# Sheet___2025-11-01.net
KiCad netlist of a schematic drawn in Altium Designer
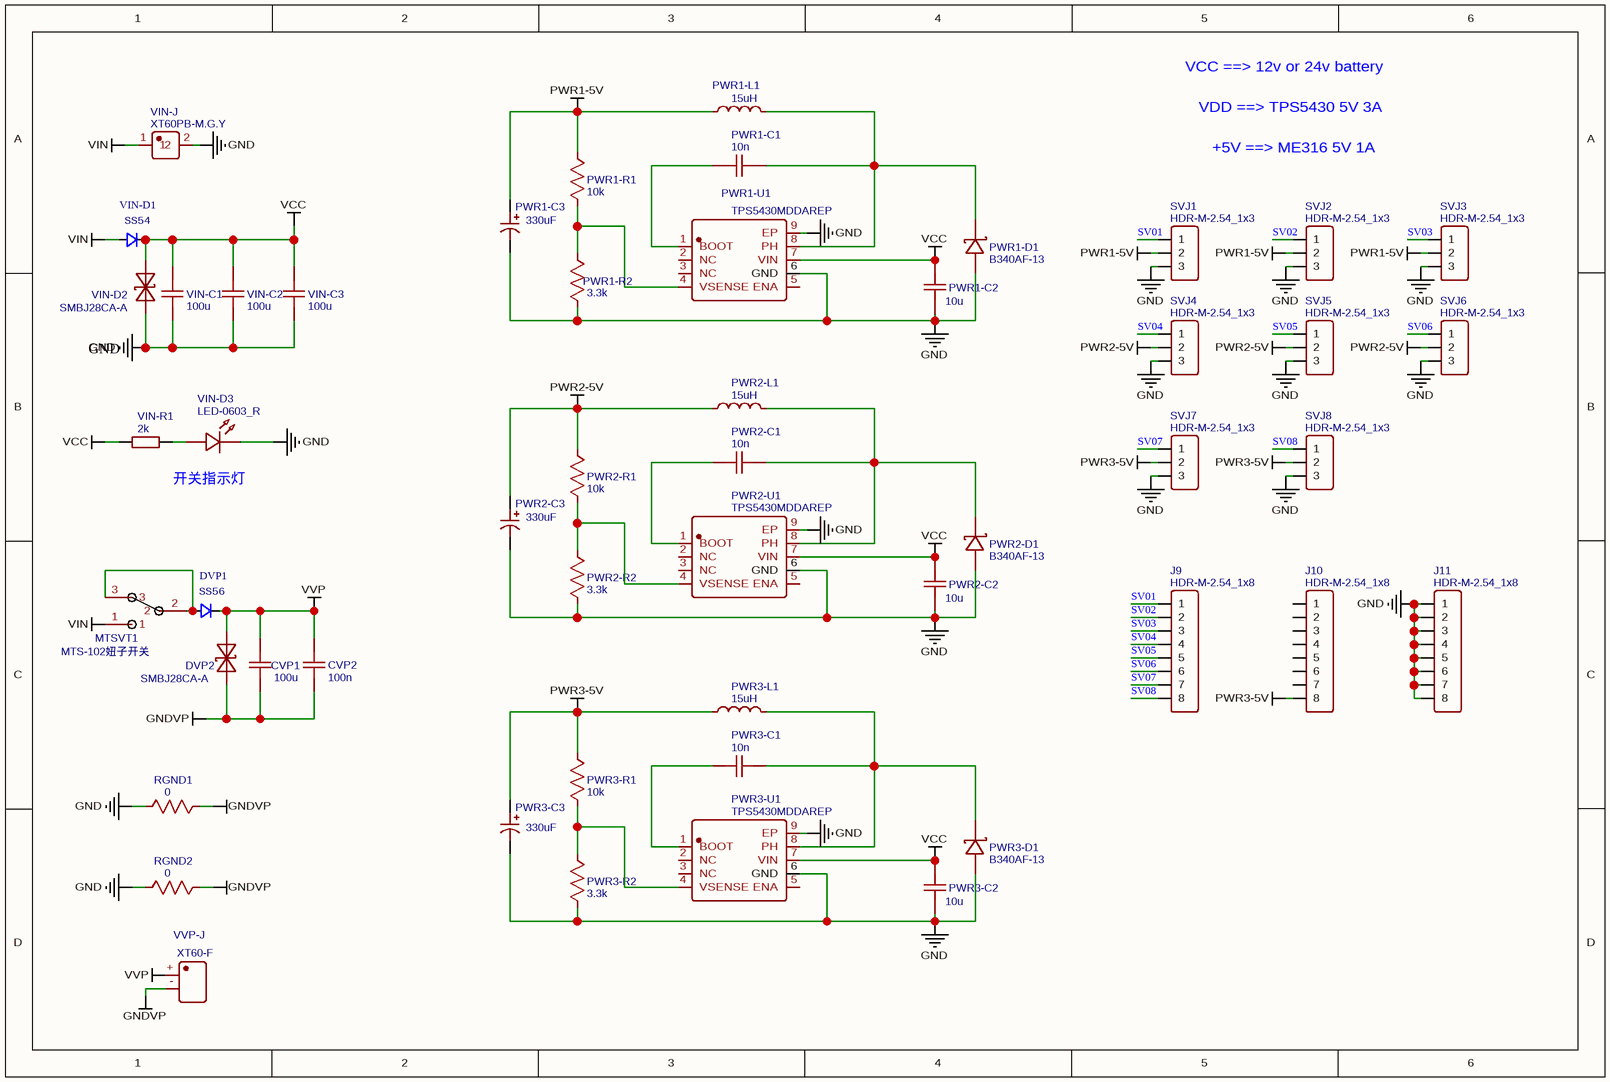
[diagram p0: Sheet_象鼻吸盘电源电路_2025-11-01.schdoc]

(export (version "E")
  (design (tool "Eeschema 10.0.6"))
  (components
    (comp (ref "CVP1")
      (value "100u")
      (fields (field (name "CONTRIBUTOR") "LCEDA_Lib"))
      (libsource (lib "altium-import") (part "root_1_100u_"))
    )
    (comp (ref "CVP2")
      (value "100n")
      (fields (field (name "CONTRIBUTOR") "LCEDA_Lib"))
      (libsource (lib "altium-import") (part "root_1_100n_"))
    )
    (comp (ref "DVP1") (value "SS56") (libsource (lib "altium-import") (part "root_0_SS56_")))
    (comp (ref "DVP2")
      (value "SMBJ28CA-A")
      (fields
        (field (name "MANUFACTURER") "SMC(Sangdest Microelectronicstronic (Nanjing))")
        (field (name "CONTRIBUTOR") "MRTAN")
      )
      (libsource (lib "altium-import") (part "root_3_SMBJ28CA-A_"))
    )
    (comp (ref "J9")
      (value "HDR-M-2.54_1x8")
      (fields (field (name "CONTRIBUTOR") "LCEDA_Lib"))
      (libsource (lib "altium-import") (part "root_0_HDR-M-2.54_1x8_"))
    )
    (comp (ref "J10")
      (value "HDR-M-2.54_1x8")
      (fields (field (name "CONTRIBUTOR") "LCEDA_Lib"))
      (libsource (lib "altium-import") (part "root_0_HDR-M-2.54_1x8_"))
    )
    (comp (ref "J11")
      (value "HDR-M-2.54_1x8")
      (fields (field (name "CONTRIBUTOR") "LCEDA_Lib"))
      (libsource (lib "altium-import") (part "root_0_HDR-M-2.54_1x8_"))
    )
    (comp (ref "MTSVT1")
      (value "MTS-102妞子开关")
      (fields (field (name "CONTRIBUTOR") "qingxiaobai"))
      (libsource (lib "altium-import") (part "root_0_MTS-102妞子开关_"))
    )
    (comp (ref "PWR1-C1")
      (value "10n")
      (fields (field (name "CONTRIBUTOR") "LCEDA_Lib"))
      (libsource (lib "altium-import") (part "root_0_10n_"))
    )
    (comp (ref "PWR1-C2")
      (value "10u")
      (fields (field (name "CONTRIBUTOR") "LCEDA_Lib"))
      (libsource (lib "altium-import") (part "root_3_10u_"))
    )
    (comp (ref "PWR1-C3")
      (value "330uF")
      (fields
        (field (name "MANUFACTURER") "DMBJ(振宝佳)")
        (field (name "MANUFACTURER PART") "RVT1C331M0810 330UF 16V")
        (field (name "CONTRIBUTOR") "lcsc")
      )
      (libsource (lib "altium-import") (part "root_3_330uF_"))
    )
    (comp (ref "PWR1-D1")
      (value "B340AF-13")
      (fields (field (name "MANUFACTURER") "DIODES(美台)") (field (name "CONTRIBUTOR") "LCSC"))
      (libsource (lib "altium-import") (part "root_3_B340AF-13_"))
    )
    (comp (ref "PWR1-L1")
      (value "15uH")
      (fields
        (field (name "MANUFACTURER") "KOHERelec(科或)")
        (field (name "MANUFACTURER PART") "MDA1050-150M")
        (field (name "CONTRIBUTOR") "lcsc")
      )
      (libsource (lib "altium-import") (part "root_0_15uH_"))
    )
    (comp (ref "PWR1-R1")
      (value "10k")
      (fields (field (name "CONTRIBUTOR") "LCEDA_Lib"))
      (libsource (lib "altium-import") (part "root_1_10k_"))
    )
    (comp (ref "PWR1-R2")
      (value "3.3k")
      (fields (field (name "CONTRIBUTOR") "LCEDA_Lib"))
      (libsource (lib "altium-import") (part "root_1_3.3k_"))
    )
    (comp (ref "PWR1-U1")
      (value "TPS5430MDDAREP")
      (fields (field (name "MANUFACTURER") "TI(德州仪器)") (field (name "CONTRIBUTOR") "LCSC"))
      (libsource (lib "altium-import") (part "root_0_TPS5430MDDAREP_"))
    )
    (comp (ref "PWR2-C1")
      (value "10n")
      (fields (field (name "CONTRIBUTOR") "LCEDA_Lib"))
      (libsource (lib "altium-import") (part "root_0_10n_"))
    )
    (comp (ref "PWR2-C2")
      (value "10u")
      (fields (field (name "CONTRIBUTOR") "LCEDA_Lib"))
      (libsource (lib "altium-import") (part "root_3_10u_"))
    )
    (comp (ref "PWR2-C3")
      (value "330uF")
      (fields
        (field (name "MANUFACTURER") "DMBJ(振宝佳)")
        (field (name "MANUFACTURER PART") "RVT1C331M0810 330UF 16V")
        (field (name "CONTRIBUTOR") "lcsc")
      )
      (libsource (lib "altium-import") (part "root_3_330uF_"))
    )
    (comp (ref "PWR2-D1")
      (value "B340AF-13")
      (fields (field (name "MANUFACTURER") "DIODES(美台)") (field (name "CONTRIBUTOR") "LCSC"))
      (libsource (lib "altium-import") (part "root_3_B340AF-13_"))
    )
    (comp (ref "PWR2-L1")
      (value "15uH")
      (fields
        (field (name "MANUFACTURER") "KOHERelec(科或)")
        (field (name "MANUFACTURER PART") "MDA1050-150M")
        (field (name "CONTRIBUTOR") "lcsc")
      )
      (libsource (lib "altium-import") (part "root_0_15uH_"))
    )
    (comp (ref "PWR2-R1")
      (value "10k")
      (fields (field (name "CONTRIBUTOR") "LCEDA_Lib"))
      (libsource (lib "altium-import") (part "root_1_10k_"))
    )
    (comp (ref "PWR2-R2")
      (value "3.3k")
      (fields (field (name "CONTRIBUTOR") "LCEDA_Lib"))
      (libsource (lib "altium-import") (part "root_1_3.3k_"))
    )
    (comp (ref "PWR2-U1")
      (value "TPS5430MDDAREP")
      (fields (field (name "MANUFACTURER") "TI(德州仪器)") (field (name "CONTRIBUTOR") "LCSC"))
      (libsource (lib "altium-import") (part "root_0_TPS5430MDDAREP_"))
    )
    (comp (ref "PWR3-C1")
      (value "10n")
      (fields (field (name "CONTRIBUTOR") "LCEDA_Lib"))
      (libsource (lib "altium-import") (part "root_0_10n_"))
    )
    (comp (ref "PWR3-C2")
      (value "10u")
      (fields (field (name "CONTRIBUTOR") "LCEDA_Lib"))
      (libsource (lib "altium-import") (part "root_3_10u_"))
    )
    (comp (ref "PWR3-C3")
      (value "330uF")
      (fields
        (field (name "MANUFACTURER") "DMBJ(振宝佳)")
        (field (name "MANUFACTURER PART") "RVT1C331M0810 330UF 16V")
        (field (name "CONTRIBUTOR") "lcsc")
      )
      (libsource (lib "altium-import") (part "root_3_330uF_"))
    )
    (comp (ref "PWR3-D1")
      (value "B340AF-13")
      (fields (field (name "MANUFACTURER") "DIODES(美台)") (field (name "CONTRIBUTOR") "LCSC"))
      (libsource (lib "altium-import") (part "root_3_B340AF-13_"))
    )
    (comp (ref "PWR3-L1")
      (value "15uH")
      (fields
        (field (name "MANUFACTURER") "KOHERelec(科或)")
        (field (name "MANUFACTURER PART") "MDA1050-150M")
        (field (name "CONTRIBUTOR") "lcsc")
      )
      (libsource (lib "altium-import") (part "root_0_15uH_"))
    )
    (comp (ref "PWR3-R1")
      (value "10k")
      (fields (field (name "CONTRIBUTOR") "LCEDA_Lib"))
      (libsource (lib "altium-import") (part "root_1_10k_"))
    )
    (comp (ref "PWR3-R2")
      (value "3.3k")
      (fields (field (name "CONTRIBUTOR") "LCEDA_Lib"))
      (libsource (lib "altium-import") (part "root_1_3.3k_"))
    )
    (comp (ref "PWR3-U1")
      (value "TPS5430MDDAREP")
      (fields (field (name "MANUFACTURER") "TI(德州仪器)") (field (name "CONTRIBUTOR") "LCSC"))
      (libsource (lib "altium-import") (part "root_0_TPS5430MDDAREP_"))
    )
    (comp (ref "RGND1")
      (value "0")
      (fields (field (name "CONTRIBUTOR") "LCEDA_Lib"))
      (libsource (lib "altium-import") (part "root_0_0_"))
    )
    (comp (ref "RGND2")
      (value "0")
      (fields (field (name "CONTRIBUTOR") "LCEDA_Lib"))
      (libsource (lib "altium-import") (part "root_0_0_"))
    )
    (comp (ref "SVJ1")
      (value "HDR-M-2.54_1x3")
      (fields (field (name "CONTRIBUTOR") "LCEDA_Lib"))
      (libsource (lib "altium-import") (part "root_0_HDR-M-2.54_1x3_"))
    )
    (comp (ref "SVJ2")
      (value "HDR-M-2.54_1x3")
      (fields (field (name "CONTRIBUTOR") "LCEDA_Lib"))
      (libsource (lib "altium-import") (part "root_0_HDR-M-2.54_1x3_"))
    )
    (comp (ref "SVJ3")
      (value "HDR-M-2.54_1x3")
      (fields (field (name "CONTRIBUTOR") "LCEDA_Lib"))
      (libsource (lib "altium-import") (part "root_0_HDR-M-2.54_1x3_"))
    )
    (comp (ref "SVJ4")
      (value "HDR-M-2.54_1x3")
      (fields (field (name "CONTRIBUTOR") "LCEDA_Lib"))
      (libsource (lib "altium-import") (part "root_0_HDR-M-2.54_1x3_"))
    )
    (comp (ref "SVJ5")
      (value "HDR-M-2.54_1x3")
      (fields (field (name "CONTRIBUTOR") "LCEDA_Lib"))
      (libsource (lib "altium-import") (part "root_0_HDR-M-2.54_1x3_"))
    )
    (comp (ref "SVJ6")
      (value "HDR-M-2.54_1x3")
      (fields (field (name "CONTRIBUTOR") "LCEDA_Lib"))
      (libsource (lib "altium-import") (part "root_0_HDR-M-2.54_1x3_"))
    )
    (comp (ref "SVJ7")
      (value "HDR-M-2.54_1x3")
      (fields (field (name "CONTRIBUTOR") "LCEDA_Lib"))
      (libsource (lib "altium-import") (part "root_0_HDR-M-2.54_1x3_"))
    )
    (comp (ref "SVJ8")
      (value "HDR-M-2.54_1x3")
      (fields (field (name "CONTRIBUTOR") "LCEDA_Lib"))
      (libsource (lib "altium-import") (part "root_0_HDR-M-2.54_1x3_"))
    )
    (comp (ref "VIN-C1")
      (value "100u")
      (fields (field (name "CONTRIBUTOR") "LCEDA_Lib"))
      (libsource (lib "altium-import") (part "root_1_100u_"))
    )
    (comp (ref "VIN-C2")
      (value "100u")
      (fields (field (name "CONTRIBUTOR") "LCEDA_Lib"))
      (libsource (lib "altium-import") (part "root_1_100u_"))
    )
    (comp (ref "VIN-C3")
      (value "100u")
      (fields (field (name "CONTRIBUTOR") "LCEDA_Lib"))
      (libsource (lib "altium-import") (part "root_1_100u_"))
    )
    (comp (ref "VIN-D1") (value "SS54") (libsource (lib "altium-import") (part "root_0_SS54_")))
    (comp (ref "VIN-D2")
      (value "SMBJ28CA-A")
      (fields
        (field (name "MANUFACTURER") "SMC(Sangdest Microelectronicstronic (Nanjing))")
        (field (name "CONTRIBUTOR") "MRTAN")
      )
      (libsource (lib "altium-import") (part "root_3_SMBJ28CA-A_"))
    )
    (comp (ref "VIN-D3")
      (value "LED-0603_R")
      (fields
        (field (name "MANUFACTURER") "EVERLIGHT(台湾亿光)")
        (field (name "MANUFACTURER PART") "19-217/R6C-AL1M2VY/3T")
        (field (name "CONTRIBUTOR") "LCEDA_01")
      )
      (libsource (lib "altium-import") (part "root_0_LED-0603_R_"))
    )
    (comp (ref "VIN-J")
      (value "XT60PB-M.G.Y")
      (fields (field (name "MANUFACTURER") "AMASS(艾迈斯)") (field (name "CONTRIBUTOR") "lcsc"))
      (libsource (lib "altium-import") (part "root_0_XT60PB-M.G.Y_"))
    )
    (comp (ref "VIN-R1")
      (value "2k")
      (fields (field (name "MANUFACTURER") "UniOhm") (field (name "MANUFACTURER PART") "0603WAF4701T5E"))
      (libsource (lib "altium-import") (part "root_2_2k_"))
    )
    (comp (ref "VVP-J")
      (value "XT60-F")
      (fields (field (name "MANUFACTURER") "AMASS(艾迈斯)") (field (name "CONTRIBUTOR") "lcsc"))
      (libsource (lib "altium-import") (part "root_0_XT60-F_"))
    )
  )
  (nets
    (net (code "1") (name "/SV01") (class "Default")
      (node (ref "J9") (pin "1") (pinfunction "1_1") (pintype "passive"))
      (node (ref "SVJ1") (pin "1") (pinfunction "1_1") (pintype "passive"))
    )
    (net (code "2") (name "/SV02") (class "Default")
      (node (ref "J9") (pin "2") (pinfunction "2_2") (pintype "passive"))
      (node (ref "SVJ2") (pin "1") (pinfunction "1_1") (pintype "passive"))
    )
    (net (code "3") (name "/SV03") (class "Default")
      (node (ref "J9") (pin "3") (pinfunction "3_3") (pintype "passive"))
      (node (ref "SVJ3") (pin "1") (pinfunction "1_1") (pintype "passive"))
    )
    (net (code "4") (name "/SV04") (class "Default")
      (node (ref "J9") (pin "4") (pinfunction "4_4") (pintype "passive"))
      (node (ref "SVJ4") (pin "1") (pinfunction "1_1") (pintype "passive"))
    )
    (net (code "5") (name "/SV05") (class "Default")
      (node (ref "J9") (pin "5") (pinfunction "5_5") (pintype "passive"))
      (node (ref "SVJ5") (pin "1") (pinfunction "1_1") (pintype "passive"))
    )
    (net (code "6") (name "/SV06") (class "Default")
      (node (ref "J9") (pin "6") (pinfunction "6_6") (pintype "passive"))
      (node (ref "SVJ6") (pin "1") (pinfunction "1_1") (pintype "passive"))
    )
    (net (code "7") (name "/SV07") (class "Default")
      (node (ref "J9") (pin "7") (pinfunction "7_7") (pintype "passive"))
      (node (ref "SVJ7") (pin "1") (pinfunction "1_1") (pintype "passive"))
    )
    (net (code "8") (name "/SV08") (class "Default")
      (node (ref "J9") (pin "8") (pinfunction "8_8") (pintype "passive"))
      (node (ref "SVJ8") (pin "1") (pinfunction "1_1") (pintype "passive"))
    )
    (net (code "9") (name "GND") (class "Default")
      (node (ref "J11") (pin "1") (pinfunction "1_1") (pintype "passive"))
      (node (ref "J11") (pin "2") (pinfunction "2_2") (pintype "passive"))
      (node (ref "J11") (pin "3") (pinfunction "3_3") (pintype "passive"))
      (node (ref "J11") (pin "4") (pinfunction "4_4") (pintype "passive"))
      (node (ref "J11") (pin "5") (pinfunction "5_5") (pintype "passive"))
      (node (ref "J11") (pin "6") (pinfunction "6_6") (pintype "passive"))
      (node (ref "J11") (pin "7") (pinfunction "7_7") (pintype "passive"))
      (node (ref "J11") (pin "8") (pinfunction "8_8") (pintype "passive"))
      (node (ref "PWR1-C2") (pin "2") (pinfunction "2_2") (pintype "passive"))
      (node (ref "PWR1-C3") (pin "2") (pinfunction "2_2") (pintype "passive"))
      (node (ref "PWR1-D1") (pin "2") (pinfunction "A_2") (pintype "passive"))
      (node (ref "PWR1-R2") (pin "1") (pinfunction "1_1") (pintype "passive"))
      (node (ref "PWR1-U1") (pin "6") (pinfunction "GND_6") (pintype "passive"))
      (node (ref "PWR1-U1") (pin "9") (pinfunction "EP_9") (pintype "passive"))
      (node (ref "PWR2-C2") (pin "2") (pinfunction "2_2") (pintype "passive"))
      (node (ref "PWR2-C3") (pin "2") (pinfunction "2_2") (pintype "passive"))
      (node (ref "PWR2-D1") (pin "2") (pinfunction "A_2") (pintype "passive"))
      (node (ref "PWR2-R2") (pin "1") (pinfunction "1_1") (pintype "passive"))
      (node (ref "PWR2-U1") (pin "6") (pinfunction "GND_6") (pintype "passive"))
      (node (ref "PWR2-U1") (pin "9") (pinfunction "EP_9") (pintype "passive"))
      (node (ref "PWR3-C2") (pin "2") (pinfunction "2_2") (pintype "passive"))
      (node (ref "PWR3-C3") (pin "2") (pinfunction "2_2") (pintype "passive"))
      (node (ref "PWR3-D1") (pin "2") (pinfunction "A_2") (pintype "passive"))
      (node (ref "PWR3-R2") (pin "1") (pinfunction "1_1") (pintype "passive"))
      (node (ref "PWR3-U1") (pin "6") (pinfunction "GND_6") (pintype "passive"))
      (node (ref "PWR3-U1") (pin "9") (pinfunction "EP_9") (pintype "passive"))
      (node (ref "RGND1") (pin "1") (pinfunction "1_1") (pintype "passive"))
      (node (ref "RGND2") (pin "1") (pinfunction "1_1") (pintype "passive"))
      (node (ref "SVJ1") (pin "3") (pinfunction "3_3") (pintype "passive"))
      (node (ref "SVJ2") (pin "3") (pinfunction "3_3") (pintype "passive"))
      (node (ref "SVJ3") (pin "3") (pinfunction "3_3") (pintype "passive"))
      (node (ref "SVJ4") (pin "3") (pinfunction "3_3") (pintype "passive"))
      (node (ref "SVJ5") (pin "3") (pinfunction "3_3") (pintype "passive"))
      (node (ref "SVJ6") (pin "3") (pinfunction "3_3") (pintype "passive"))
      (node (ref "SVJ7") (pin "3") (pinfunction "3_3") (pintype "passive"))
      (node (ref "SVJ8") (pin "3") (pinfunction "3_3") (pintype "passive"))
      (node (ref "VIN-C1") (pin "1") (pinfunction "1_1") (pintype "passive"))
      (node (ref "VIN-C2") (pin "1") (pinfunction "1_1") (pintype "passive"))
      (node (ref "VIN-C3") (pin "1") (pinfunction "1_1") (pintype "passive"))
      (node (ref "VIN-D2") (pin "2") (pinfunction "2_2") (pintype "passive"))
      (node (ref "VIN-D3") (pin "2") (pinfunction "2_2") (pintype "passive"))
      (node (ref "VIN-J") (pin "2") (pinfunction "2_2") (pintype "passive"))
    )
    (net (code "10") (name "GNDVP") (class "Default")
      (node (ref "CVP1") (pin "1") (pinfunction "1_1") (pintype "passive"))
      (node (ref "CVP2") (pin "1") (pinfunction "1_1") (pintype "passive"))
      (node (ref "DVP2") (pin "2") (pinfunction "2_2") (pintype "passive"))
      (node (ref "RGND1") (pin "2") (pinfunction "2_2") (pintype "passive"))
      (node (ref "RGND2") (pin "2") (pinfunction "2_2") (pintype "passive"))
      (node (ref "VVP-J") (pin "-") (pinfunction "2_-") (pintype "passive"))
    )
    (net (code "11") (name "Net-(DVP1-A)") (class "Default")
      (node (ref "DVP1") (pin "2") (pinfunction "A_2") (pintype "passive"))
      (node (ref "MTSVT1") (pin "2") (pinfunction "2_2") (pintype "passive"))
      (node (ref "MTSVT1") (pin "3") (pinfunction "3_3") (pintype "passive"))
    )
    (net (code "12") (name "Net-(PWR1-D1-C)") (class "Default")
      (node (ref "PWR1-C1") (pin "2") (pinfunction "2_2") (pintype "passive"))
      (node (ref "PWR1-D1") (pin "1") (pinfunction "C_1") (pintype "passive"))
      (node (ref "PWR1-L1") (pin "2") (pinfunction "2_2") (pintype "passive"))
      (node (ref "PWR1-U1") (pin "8") (pinfunction "PH_8") (pintype "passive"))
    )
    (net (code "13") (name "Net-(PWR1-U1-BOOT)") (class "Default")
      (node (ref "PWR1-C1") (pin "1") (pinfunction "1_1") (pintype "passive"))
      (node (ref "PWR1-U1") (pin "1") (pinfunction "BOOT_1") (pintype "passive"))
    )
    (net (code "14") (name "Net-(PWR1-U1-VSENSE)") (class "Default")
      (node (ref "PWR1-R1") (pin "1") (pinfunction "1_1") (pintype "passive"))
      (node (ref "PWR1-R2") (pin "2") (pinfunction "2_2") (pintype "passive"))
      (node (ref "PWR1-U1") (pin "4") (pinfunction "VSENSE_4") (pintype "passive"))
    )
    (net (code "15") (name "Net-(PWR2-D1-C)") (class "Default")
      (node (ref "PWR2-C1") (pin "2") (pinfunction "2_2") (pintype "passive"))
      (node (ref "PWR2-D1") (pin "1") (pinfunction "C_1") (pintype "passive"))
      (node (ref "PWR2-L1") (pin "2") (pinfunction "2_2") (pintype "passive"))
      (node (ref "PWR2-U1") (pin "8") (pinfunction "PH_8") (pintype "passive"))
    )
    (net (code "16") (name "Net-(PWR2-U1-BOOT)") (class "Default")
      (node (ref "PWR2-C1") (pin "1") (pinfunction "1_1") (pintype "passive"))
      (node (ref "PWR2-U1") (pin "1") (pinfunction "BOOT_1") (pintype "passive"))
    )
    (net (code "17") (name "Net-(PWR2-U1-VSENSE)") (class "Default")
      (node (ref "PWR2-R1") (pin "1") (pinfunction "1_1") (pintype "passive"))
      (node (ref "PWR2-R2") (pin "2") (pinfunction "2_2") (pintype "passive"))
      (node (ref "PWR2-U1") (pin "4") (pinfunction "VSENSE_4") (pintype "passive"))
    )
    (net (code "18") (name "Net-(PWR3-D1-C)") (class "Default")
      (node (ref "PWR3-C1") (pin "2") (pinfunction "2_2") (pintype "passive"))
      (node (ref "PWR3-D1") (pin "1") (pinfunction "C_1") (pintype "passive"))
      (node (ref "PWR3-L1") (pin "2") (pinfunction "2_2") (pintype "passive"))
      (node (ref "PWR3-U1") (pin "8") (pinfunction "PH_8") (pintype "passive"))
    )
    (net (code "19") (name "Net-(PWR3-U1-BOOT)") (class "Default")
      (node (ref "PWR3-C1") (pin "1") (pinfunction "1_1") (pintype "passive"))
      (node (ref "PWR3-U1") (pin "1") (pinfunction "BOOT_1") (pintype "passive"))
    )
    (net (code "20") (name "Net-(PWR3-U1-VSENSE)") (class "Default")
      (node (ref "PWR3-R1") (pin "1") (pinfunction "1_1") (pintype "passive"))
      (node (ref "PWR3-R2") (pin "2") (pinfunction "2_2") (pintype "passive"))
      (node (ref "PWR3-U1") (pin "4") (pinfunction "VSENSE_4") (pintype "passive"))
    )
    (net (code "21") (name "Net-(VIN-D3-Pad1)") (class "Default")
      (node (ref "VIN-D3") (pin "1") (pinfunction "1_1") (pintype "passive"))
      (node (ref "VIN-R1") (pin "1") (pinfunction "1_1") (pintype "passive"))
    )
    (net (code "22") (name "PWR1-5V") (class "Default")
      (node (ref "PWR1-C3") (pin "1") (pinfunction "1_1") (pintype "passive"))
      (node (ref "PWR1-L1") (pin "1") (pinfunction "1_1") (pintype "passive"))
      (node (ref "PWR1-R1") (pin "2") (pinfunction "2_2") (pintype "passive"))
      (node (ref "SVJ1") (pin "2") (pinfunction "2_2") (pintype "passive"))
      (node (ref "SVJ2") (pin "2") (pinfunction "2_2") (pintype "passive"))
      (node (ref "SVJ3") (pin "2") (pinfunction "2_2") (pintype "passive"))
    )
    (net (code "23") (name "PWR2-5V") (class "Default")
      (node (ref "PWR2-C3") (pin "1") (pinfunction "1_1") (pintype "passive"))
      (node (ref "PWR2-L1") (pin "1") (pinfunction "1_1") (pintype "passive"))
      (node (ref "PWR2-R1") (pin "2") (pinfunction "2_2") (pintype "passive"))
      (node (ref "SVJ4") (pin "2") (pinfunction "2_2") (pintype "passive"))
      (node (ref "SVJ5") (pin "2") (pinfunction "2_2") (pintype "passive"))
      (node (ref "SVJ6") (pin "2") (pinfunction "2_2") (pintype "passive"))
    )
    (net (code "24") (name "PWR3-5V") (class "Default")
      (node (ref "J10") (pin "8") (pinfunction "8_8") (pintype "passive"))
      (node (ref "PWR3-C3") (pin "1") (pinfunction "1_1") (pintype "passive"))
      (node (ref "PWR3-L1") (pin "1") (pinfunction "1_1") (pintype "passive"))
      (node (ref "PWR3-R1") (pin "2") (pinfunction "2_2") (pintype "passive"))
      (node (ref "SVJ7") (pin "2") (pinfunction "2_2") (pintype "passive"))
      (node (ref "SVJ8") (pin "2") (pinfunction "2_2") (pintype "passive"))
    )
    (net (code "25") (name "VCC") (class "Default")
      (node (ref "PWR1-C2") (pin "1") (pinfunction "1_1") (pintype "passive"))
      (node (ref "PWR1-U1") (pin "7") (pinfunction "VIN_7") (pintype "passive"))
      (node (ref "PWR2-C2") (pin "1") (pinfunction "1_1") (pintype "passive"))
      (node (ref "PWR2-U1") (pin "7") (pinfunction "VIN_7") (pintype "passive"))
      (node (ref "PWR3-C2") (pin "1") (pinfunction "1_1") (pintype "passive"))
      (node (ref "PWR3-U1") (pin "7") (pinfunction "VIN_7") (pintype "passive"))
      (node (ref "VIN-C1") (pin "2") (pinfunction "2_2") (pintype "passive"))
      (node (ref "VIN-C2") (pin "2") (pinfunction "2_2") (pintype "passive"))
      (node (ref "VIN-C3") (pin "2") (pinfunction "2_2") (pintype "passive"))
      (node (ref "VIN-D1") (pin "1") (pinfunction "K_1") (pintype "passive"))
      (node (ref "VIN-D2") (pin "1") (pinfunction "1_1") (pintype "passive"))
      (node (ref "VIN-R1") (pin "2") (pinfunction "2_2") (pintype "passive"))
    )
    (net (code "26") (name "VIN") (class "Default")
      (node (ref "MTSVT1") (pin "1") (pinfunction "1_1") (pintype "passive"))
      (node (ref "VIN-D1") (pin "2") (pinfunction "A_2") (pintype "passive"))
      (node (ref "VIN-J") (pin "1") (pinfunction "1_1") (pintype "passive"))
    )
    (net (code "27") (name "VVP") (class "Default")
      (node (ref "CVP1") (pin "2") (pinfunction "2_2") (pintype "passive"))
      (node (ref "CVP2") (pin "2") (pinfunction "2_2") (pintype "passive"))
      (node (ref "DVP1") (pin "1") (pinfunction "K_1") (pintype "passive"))
      (node (ref "DVP2") (pin "1") (pinfunction "1_1") (pintype "passive"))
      (node (ref "VVP-J") (pin "+") (pinfunction "1_+") (pintype "passive"))
    )
    (net (code "28") (name "unconnected-(J10-Pad1)") (class "Default")
      (node (ref "J10") (pin "1") (pinfunction "1_1") (pintype "passive"))
    )
    (net (code "29") (name "unconnected-(J10-Pad2)") (class "Default")
      (node (ref "J10") (pin "2") (pinfunction "2_2") (pintype "passive"))
    )
    (net (code "30") (name "unconnected-(J10-Pad3)") (class "Default")
      (node (ref "J10") (pin "3") (pinfunction "3_3") (pintype "passive"))
    )
    (net (code "31") (name "unconnected-(J10-Pad4)") (class "Default")
      (node (ref "J10") (pin "4") (pinfunction "4_4") (pintype "passive"))
    )
    (net (code "32") (name "unconnected-(J10-Pad5)") (class "Default")
      (node (ref "J10") (pin "5") (pinfunction "5_5") (pintype "passive"))
    )
    (net (code "33") (name "unconnected-(J10-Pad6)") (class "Default")
      (node (ref "J10") (pin "6") (pinfunction "6_6") (pintype "passive"))
    )
    (net (code "34") (name "unconnected-(J10-Pad7)") (class "Default")
      (node (ref "J10") (pin "7") (pinfunction "7_7") (pintype "passive"))
    )
    (net (code "35") (name "unconnected-(PWR1-U1-ENA-Pad5)") (class "Default")
      (node (ref "PWR1-U1") (pin "5") (pinfunction "ENA_5") (pintype "passive"))
    )
    (net (code "36") (name "unconnected-(PWR1-U1-NC-Pad2)") (class "Default")
      (node (ref "PWR1-U1") (pin "2") (pinfunction "NC_2") (pintype "passive"))
    )
    (net (code "37") (name "unconnected-(PWR1-U1-NC-Pad3)") (class "Default")
      (node (ref "PWR1-U1") (pin "3") (pinfunction "NC_3") (pintype "passive"))
    )
    (net (code "38") (name "unconnected-(PWR2-U1-ENA-Pad5)") (class "Default")
      (node (ref "PWR2-U1") (pin "5") (pinfunction "ENA_5") (pintype "passive"))
    )
    (net (code "39") (name "unconnected-(PWR2-U1-NC-Pad2)") (class "Default")
      (node (ref "PWR2-U1") (pin "2") (pinfunction "NC_2") (pintype "passive"))
    )
    (net (code "40") (name "unconnected-(PWR2-U1-NC-Pad3)") (class "Default")
      (node (ref "PWR2-U1") (pin "3") (pinfunction "NC_3") (pintype "passive"))
    )
    (net (code "41") (name "unconnected-(PWR3-U1-ENA-Pad5)") (class "Default")
      (node (ref "PWR3-U1") (pin "5") (pinfunction "ENA_5") (pintype "passive"))
    )
    (net (code "42") (name "unconnected-(PWR3-U1-NC-Pad2)") (class "Default")
      (node (ref "PWR3-U1") (pin "2") (pinfunction "NC_2") (pintype "passive"))
    )
    (net (code "43") (name "unconnected-(PWR3-U1-NC-Pad3)") (class "Default")
      (node (ref "PWR3-U1") (pin "3") (pinfunction "NC_3") (pintype "passive"))
    )
  )
)
